# EDA_AD__2021-08-16.net
KiCad netlist of a schematic drawn in Altium Designer
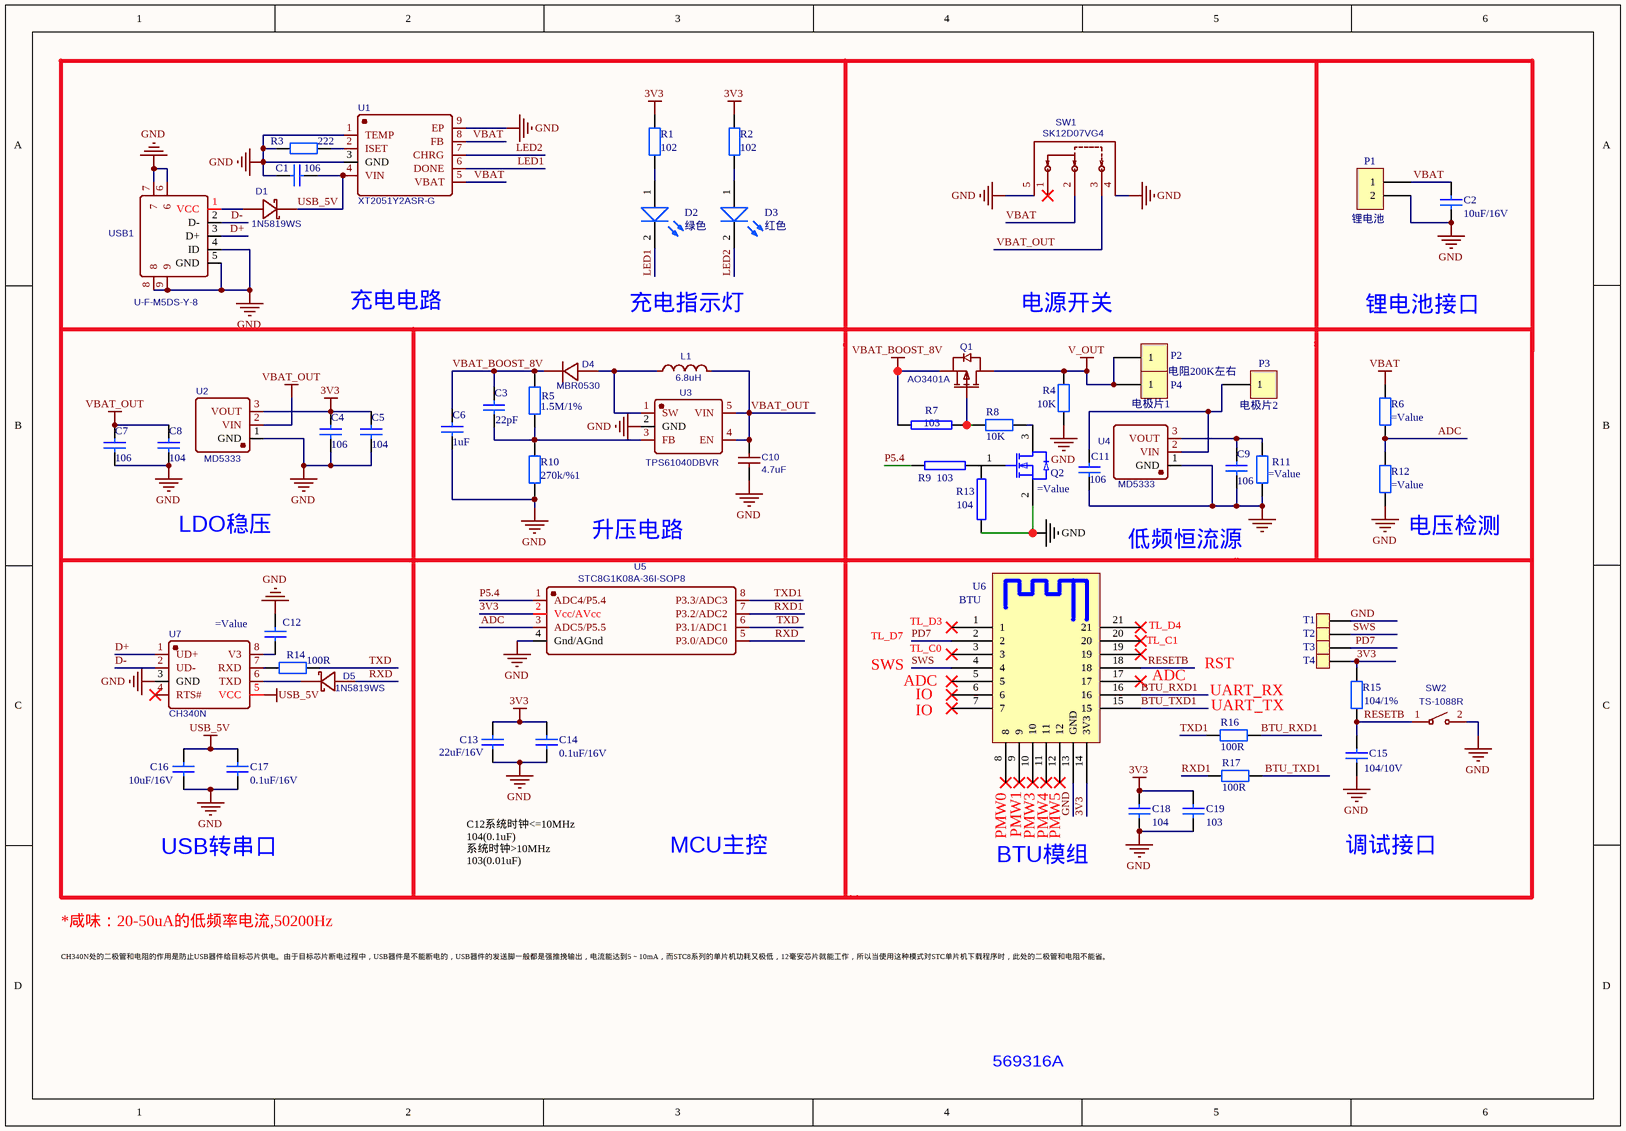
[diagram p0: 百味勺子（立创EDA、AD）_2021-08-16.schdoc]

(export (version "E")
  (design (tool "Eeschema 10.0.6"))
  (components
    (comp (ref "C1")
      (value "1uF/16V")
      (fields (field (name "PART NUMBER") "1.02.03.00181") (field (name "修改人") "system"))
      (libsource (lib "altium-import") (part "root_2_1uF/16V_"))
    )
    (comp (ref "C2")
      (value "10uF/16V")
      (fields (field (name "PART NUMBER") "1.02.05.00869"))
      (libsource (lib "altium-import") (part "root_3_10uF/16V_"))
    )
    (comp (ref "C3")
      (value "22pF")
      (fields (field (name "PART NUMBER") "1.02.05.00869"))
      (libsource (lib "altium-import") (part "root_3_22pF_"))
    )
    (comp (ref "C4")
      (value "106")
      (fields (field (name "PART NUMBER") "1.02.05.00869"))
      (libsource (lib "altium-import") (part "root_3_106_"))
    )
    (comp (ref "C5")
      (value "104")
      (fields (field (name "PART NUMBER") "1.02.05.00869"))
      (libsource (lib "altium-import") (part "root_3_104_"))
    )
    (comp (ref "C6")
      (value "1uF")
      (fields (field (name "PART NUMBER") "1.02.05.00869"))
      (libsource (lib "altium-import") (part "root_3_1uF_"))
    )
    (comp (ref "C7")
      (value "106")
      (fields (field (name "PART NUMBER") "1.02.05.00869"))
      (libsource (lib "altium-import") (part "root_3_106_"))
    )
    (comp (ref "C8")
      (value "104")
      (fields (field (name "PART NUMBER") "1.02.05.00869"))
      (libsource (lib "altium-import") (part "root_3_104_"))
    )
    (comp (ref "C9")
      (value "106")
      (fields (field (name "PART NUMBER") "1.02.05.00869"))
      (libsource (lib "altium-import") (part "root_3_106_"))
    )
    (comp (ref "C10")
      (value "4.7uF")
      (fields
        (field (name "BOM_MANUFACTURER PART") "JMK212BJ475KG-T")
        (field (name "BOM_SUPPLIER PART") "C92788")
      )
      (libsource (lib "altium-import") (part "root_1_4.7uF_"))
    )
    (comp (ref "C11")
      (value "106")
      (fields (field (name "PART NUMBER") "1.02.05.00869"))
      (libsource (lib "altium-import") (part "root_3_106_"))
    )
    (comp (ref "C12")
      (value "0.1uF/50V")
      (fields (field (name "PART NUMBER") "1.02.05.00834") (field (name "修改人") "system"))
      (libsource (lib "altium-import") (part "root_1_0.1uF/50V_"))
    )
    (comp (ref "C13")
      (value "1uF/16V")
      (fields (field (name "PART NUMBER") "1.02.03.00181") (field (name "修改人") "system"))
      (libsource (lib "altium-import") (part "root_1_1uF/16V_"))
    )
    (comp (ref "C14")
      (value "0.1uF/50V")
      (fields (field (name "PART NUMBER") "1.02.05.00834") (field (name "修改人") "system"))
      (libsource (lib "altium-import") (part "root_1_0.1uF/50V_"))
    )
    (comp (ref "C15")
      (value "104/10V")
      (fields (field (name "PART NUMBER") "1.02.05.00869"))
      (libsource (lib "altium-import") (part "root_3_104/10V_"))
    )
    (comp (ref "C16")
      (value "1uF/16V")
      (fields (field (name "PART NUMBER") "1.02.03.00181") (field (name "修改人") "system"))
      (libsource (lib "altium-import") (part "root_1_1uF/16V_"))
    )
    (comp (ref "C17")
      (value "0.1uF/50V")
      (fields (field (name "PART NUMBER") "1.02.05.00834") (field (name "修改人") "system"))
      (libsource (lib "altium-import") (part "root_1_0.1uF/50V_"))
    )
    (comp (ref "C18")
      (value "104")
      (fields (field (name "PART NUMBER") "1.02.05.00869"))
      (libsource (lib "altium-import") (part "root_3_104_"))
    )
    (comp (ref "C19")
      (value "103")
      (fields (field (name "PART NUMBER") "1.02.05.00869"))
      (libsource (lib "altium-import") (part "root_3_103_"))
    )
    (comp (ref "D1")
      (value "1N5819WS")
      (fields (field (name "BOM_SUPPLIER PART") "C1884554") (field (name "CONTRIBUTOR") "LCSC"))
      (libsource (lib "altium-import") (part "root_2_1N5819WS_"))
    )
    (comp (ref "D2")
      (value "绿色")
      (fields (field (name "PART NUMBER") "1.06.02.00452"))
      (libsource (lib "altium-import") (part "root_3_绿色_"))
    )
    (comp (ref "D3")
      (value "红色")
      (fields (field (name "PART NUMBER") "1.06.02.00452"))
      (libsource (lib "altium-import") (part "root_3_红色_"))
    )
    (comp (ref "D4")
      (value "MBR0530")
      (fields (field (name "BOM_SUPPLIER PART") "C475718") (field (name "CONTRIBUTOR") "LCSC"))
      (libsource (lib "altium-import") (part "root_0_MBR0530_"))
    )
    (comp (ref "D5")
      (value "1N5819WS")
      (fields (field (name "BOM_SUPPLIER PART") "C1884554") (field (name "CONTRIBUTOR") "LCSC"))
      (libsource (lib "altium-import") (part "root_0_1N5819WS_"))
    )
    (comp (ref "L1")
      (value "6.8uH")
      (fields
        (field (name "BOM_SUPPLIER PART") "C323532")
        (field (name "BOM_MANUFACTURER PART") "CDRH3D23NP-6R8PC")
        (field (name "CONTRIBUTOR") "LCSC")
      )
      (libsource (lib "altium-import") (part "root_0_6.8uH_"))
    )
    (comp (ref "P1") (value "锂电池") (libsource (lib "altium-import") (part "root_0_锂电池_")))
    (comp (ref "P2") (value "CON1") (libsource (lib "altium-import") (part "root_0_CON1_")))
    (comp (ref "P3") (value "CON1") (libsource (lib "altium-import") (part "root_0_CON1_")))
    (comp (ref "P4") (value "CON1") (libsource (lib "altium-import") (part "root_0_CON1_")))
    (comp (ref "Q1")
      (value "AO3401A")
      (fields (field (name "BOM_SUPPLIER PART") "C700954") (field (name "CONTRIBUTOR") "LCSC"))
      (libsource (lib "altium-import") (part "root_1_AO3401A_"))
    )
    (comp (ref "Q2")
      (value "CJ2312")
      (fields
        (field (name "PART NUMBER") "1.06.11.00008")
        (field (name "ORCAD LIBRARY PATH") "‪Z:\\tuya_lib\\sch-lib\\DISCRETE.OLB")
        (field (name "修改人") "system")
      )
      (libsource (lib "altium-import") (part "root_0_CJ2312_"))
    )
    (comp (ref "R1")
      (value "102")
      (fields (field (name "PART NUMBER") "1.01.01.00808"))
      (libsource (lib "altium-import") (part "root_1_102_"))
    )
    (comp (ref "R2")
      (value "102")
      (fields (field (name "PART NUMBER") "1.01.01.00808"))
      (libsource (lib "altium-import") (part "root_1_102_"))
    )
    (comp (ref "R3")
      (value "222")
      (fields (field (name "PART NUMBER") "1.01.01.00808"))
      (libsource (lib "altium-import") (part "root_2_222_"))
    )
    (comp (ref "R4") (value "100K/1%") (libsource (lib "altium-import") (part "root_3_100K/1%_")))
    (comp (ref "R5") (value "100K/1%") (libsource (lib "altium-import") (part "root_1_100K/1%_")))
    (comp (ref "R6") (value "100K/1%") (libsource (lib "altium-import") (part "root_1_100K/1%_")))
    (comp (ref "R7") (value "103") (libsource (lib "altium-import") (part "root_0_103_")))
    (comp (ref "R8") (value "100K/1%") (libsource (lib "altium-import") (part "root_0_100K/1%_")))
    (comp (ref "R9") (value "103") (libsource (lib "altium-import") (part "root_0_103_")))
    (comp (ref "R10") (value "100K/1%") (libsource (lib "altium-import") (part "root_1_100K/1%_")))
    (comp (ref "R11") (value "100K/1%") (libsource (lib "altium-import") (part "root_1_100K/1%_")))
    (comp (ref "R12") (value "100K/1%") (libsource (lib "altium-import") (part "root_1_100K/1%_")))
    (comp (ref "R13") (value "104") (libsource (lib "altium-import") (part "root_1_104_")))
    (comp (ref "R14")
      (value "200R")
      (fields (field (name "PART NUMBER") "1.01.01.00808") (field (name "修改人") "system"))
      (libsource (lib "altium-import") (part "root_0_200R_"))
    )
    (comp (ref "R15")
      (value "104/1%")
      (fields (field (name "PART NUMBER") "1.01.01.00808"))
      (libsource (lib "altium-import") (part "root_1_104/1%_"))
    )
    (comp (ref "R16")
      (value "100R")
      (fields (field (name "PART NUMBER") "1.01.01.00808"))
      (libsource (lib "altium-import") (part "root_2_100R_"))
    )
    (comp (ref "R17")
      (value "100R")
      (fields (field (name "PART NUMBER") "1.01.01.00808"))
      (libsource (lib "altium-import") (part "root_2_100R_"))
    )
    (comp (ref "SW1")
      (value "SK12D07VG4")
      (fields (field (name "BOM_SUPPLIER PART") "C393937") (field (name "CONTRIBUTOR") "LCSC"))
      (libsource (lib "altium-import") (part "root_0_SK12D07VG4_"))
    )
    (comp (ref "SW2")
      (value "TS-1088R")
      (fields
        (field (name "BOM_SUPPLIER PART") "C455280")
        (field (name "BOM_MANUFACTURER PART") "TS-1088R-02026")
        (field (name "CONTRIBUTOR") "LCSC")
      )
      (libsource (lib "altium-import") (part "root_0_TS-1088R_"))
    )
    (comp (ref "T1") (value "TP") (libsource (lib "altium-import") (part "root_0_TP_")))
    (comp (ref "T2") (value "TP") (libsource (lib "altium-import") (part "root_0_TP_")))
    (comp (ref "T3") (value "TP") (libsource (lib "altium-import") (part "root_0_TP_")))
    (comp (ref "T4") (value "TP") (libsource (lib "altium-import") (part "root_0_TP_")))
    (comp (ref "U1")
      (value "XT2051Y2ASR-G")
      (fields (field (name "BOM_SUPPLIER PART") "C236398") (field (name "CONTRIBUTOR") "LCSC"))
      (libsource (lib "altium-import") (part "root_0_XT2051Y2ASR-G_"))
    )
    (comp (ref "U2")
      (value "MD5333")
      (fields (field (name "BOM_SUPPLIER PART") "C2827936") (field (name "CONTRIBUTOR") "LCSC"))
      (libsource (lib "altium-import") (part "root_2_MD5333_"))
    )
    (comp (ref "U3")
      (value "TPS61040DBVR")
      (fields (field (name "BOM_SUPPLIER PART") "C7722"))
      (libsource (lib "altium-import") (part "root_0_TPS61040DBVR_"))
    )
    (comp (ref "U4")
      (value "MD5333")
      (fields (field (name "BOM_SUPPLIER PART") "C2827936") (field (name "CONTRIBUTOR") "LCSC"))
      (libsource (lib "altium-import") (part "root_2_MD5333_"))
    )
    (comp (ref "U5")
      (value "STC8G1K08A-36I-SOP8")
      (fields (field (name "BOM_SUPPLIER PART") "C915663") (field (name "CONTRIBUTOR") "LCSC"))
      (libsource (lib "altium-import") (part "root_0_STC8G1K08A-36I-SOP8_"))
    )
    (comp (ref "U6")
      (value "CBU")
      (fields (field (name "PART NUMBER") "0110"))
      (libsource (lib "altium-import") (part "root_0_CBU_"))
    )
    (comp (ref "U7")
      (value "CH340N")
      (fields (field (name "BOM_SUPPLIER PART") "C506813") (field (name "CONTRIBUTOR") "LCSC"))
      (libsource (lib "altium-import") (part "root_0_CH340N_"))
    )
    (comp (ref "USB1")
      (value "U-F-M5DS-Y-8")
      (fields (field (name "BOM_SUPPLIER PART") "C961761") (field (name "CONTRIBUTOR") "LCSC"))
      (libsource (lib "altium-import") (part "root_0_U-F-M5DS-Y-8_"))
    )
  )
  (nets
    (net (code "1") (name "/ADC") (class "Default")
      (node (ref "R12") (pin "2") (pinfunction "2_2") (pintype "passive"))
      (node (ref "R6") (pin "1") (pinfunction "1_1") (pintype "passive"))
      (node (ref "U5") (pin "3") (pinfunction "ADC5/P5.5_3") (pintype "passive"))
    )
    (net (code "2") (name "/BTU_RXD1") (class "Default")
      (node (ref "R16") (pin "1") (pinfunction "1_1") (pintype "passive"))
      (node (ref "U6") (pin "16") (pinfunction "16_16") (pintype "passive"))
    )
    (net (code "3") (name "/BTU_TXD1") (class "Default")
      (node (ref "R17") (pin "1") (pinfunction "1_1") (pintype "passive"))
      (node (ref "U6") (pin "15") (pinfunction "15_15") (pintype "passive"))
    )
    (net (code "4") (name "/D+") (class "Default")
      (node (ref "U7") (pin "1") (pinfunction "UD+_1") (pintype "passive"))
      (node (ref "USB1") (pin "3") (pinfunction "D+_3") (pintype "passive"))
    )
    (net (code "5") (name "/D-") (class "Default")
      (node (ref "U7") (pin "2") (pinfunction "UD-_2") (pintype "passive"))
      (node (ref "USB1") (pin "2") (pinfunction "D-_2") (pintype "passive"))
    )
    (net (code "6") (name "/LED1") (class "Default")
      (node (ref "D2") (pin "2") (pinfunction "2_2") (pintype "passive"))
      (node (ref "U1") (pin "6") (pinfunction "DONE_6") (pintype "passive"))
    )
    (net (code "7") (name "/LED2") (class "Default")
      (node (ref "D3") (pin "2") (pinfunction "2_2") (pintype "passive"))
      (node (ref "U1") (pin "7") (pinfunction "CHRG_7") (pintype "passive"))
    )
    (net (code "8") (name "/P5.4") (class "Default")
      (node (ref "R9") (pin "1") (pintype "passive"))
      (node (ref "U5") (pin "1") (pinfunction "ADC4/P5.4_1") (pintype "passive"))
    )
    (net (code "9") (name "/PD7") (class "Default")
      (node (ref "T3") (pin "1") (pinfunction "1_1") (pintype "passive"))
      (node (ref "U6") (pin "2") (pinfunction "2_2") (pintype "passive"))
    )
    (net (code "10") (name "/RESETB") (class "Default")
      (node (ref "C15") (pin "1") (pinfunction "1_1") (pintype "passive"))
      (node (ref "R15") (pin "1") (pinfunction "1_1") (pintype "passive"))
      (node (ref "SW2") (pin "1") (pinfunction "1_1") (pintype "passive"))
      (node (ref "U6") (pin "18") (pinfunction "18_18") (pintype "passive"))
    )
    (net (code "11") (name "/RXD") (class "Default")
      (node (ref "D5") (pin "2") (pinfunction "A_2") (pintype "passive"))
      (node (ref "U5") (pin "5") (pinfunction "P3.0/ADC0_5") (pintype "passive"))
    )
    (net (code "12") (name "/RXD1") (class "Default")
      (node (ref "R17") (pin "2") (pinfunction "2_2") (pintype "passive"))
      (node (ref "U5") (pin "7") (pinfunction "P3.2/ADC2_7") (pintype "passive"))
    )
    (net (code "13") (name "/SWS") (class "Default")
      (node (ref "T2") (pin "1") (pinfunction "1_1") (pintype "passive"))
      (node (ref "U6") (pin "4") (pinfunction "4_4") (pintype "passive"))
    )
    (net (code "14") (name "/TXD") (class "Default")
      (node (ref "R14") (pin "2") (pinfunction "2_2") (pintype "passive"))
      (node (ref "U5") (pin "6") (pinfunction "P3.1/ADC1_6") (pintype "passive"))
    )
    (net (code "15") (name "/TXD1") (class "Default")
      (node (ref "R16") (pin "2") (pinfunction "2_2") (pintype "passive"))
      (node (ref "U5") (pin "8") (pinfunction "P3.3/ADC3_8") (pintype "passive"))
    )
    (net (code "16") (name "3V3") (class "Default")
      (node (ref "C13") (pin "2") (pinfunction "2_2") (pintype "passive"))
      (node (ref "C14") (pin "2") (pinfunction "2_2") (pintype "passive"))
      (node (ref "C18") (pin "1") (pinfunction "1_1") (pintype "passive"))
      (node (ref "C19") (pin "1") (pinfunction "1_1") (pintype "passive"))
      (node (ref "C4") (pin "1") (pinfunction "1_1") (pintype "passive"))
      (node (ref "C5") (pin "1") (pinfunction "1_1") (pintype "passive"))
      (node (ref "R1") (pin "2") (pinfunction "2_2") (pintype "passive"))
      (node (ref "R15") (pin "2") (pinfunction "2_2") (pintype "passive"))
      (node (ref "R2") (pin "2") (pinfunction "2_2") (pintype "passive"))
      (node (ref "T4") (pin "1") (pinfunction "1_1") (pintype "passive"))
      (node (ref "U2") (pin "3") (pinfunction "VOUT_3") (pintype "passive"))
      (node (ref "U5") (pin "2") (pinfunction "Vcc/AVcc_2") (pintype "passive"))
      (node (ref "U6") (pin "14") (pinfunction "3V3_14") (pintype "passive"))
    )
    (net (code "17") (name "GND") (class "Default")
      (node (ref "C1") (pin "2") (pinfunction "2_2") (pintype "passive"))
      (node (ref "C10") (pin "1") (pinfunction "1_1") (pintype "passive"))
      (node (ref "C11") (pin "2") (pinfunction "2_2") (pintype "passive"))
      (node (ref "C12") (pin "2") (pinfunction "2_2") (pintype "passive"))
      (node (ref "C13") (pin "1") (pinfunction "1_1") (pintype "passive"))
      (node (ref "C14") (pin "1") (pinfunction "1_1") (pintype "passive"))
      (node (ref "C15") (pin "2") (pinfunction "2_2") (pintype "passive"))
      (node (ref "C16") (pin "1") (pinfunction "1_1") (pintype "passive"))
      (node (ref "C17") (pin "1") (pinfunction "1_1") (pintype "passive"))
      (node (ref "C18") (pin "2") (pinfunction "2_2") (pintype "passive"))
      (node (ref "C19") (pin "2") (pinfunction "2_2") (pintype "passive"))
      (node (ref "C2") (pin "2") (pinfunction "2_2") (pintype "passive"))
      (node (ref "C4") (pin "2") (pinfunction "2_2") (pintype "passive"))
      (node (ref "C5") (pin "2") (pinfunction "2_2") (pintype "passive"))
      (node (ref "C6") (pin "2") (pinfunction "2_2") (pintype "passive"))
      (node (ref "C7") (pin "2") (pinfunction "2_2") (pintype "passive"))
      (node (ref "C8") (pin "2") (pinfunction "2_2") (pintype "passive"))
      (node (ref "C9") (pin "2") (pinfunction "2_2") (pintype "passive"))
      (node (ref "P1") (pin "2") (pinfunction "2_2") (pintype "passive"))
      (node (ref "Q2") (pin "2") (pinfunction "S_2") (pintype "passive"))
      (node (ref "R10") (pin "1") (pinfunction "1_1") (pintype "passive"))
      (node (ref "R11") (pin "1") (pinfunction "1_1") (pintype "passive"))
      (node (ref "R12") (pin "1") (pinfunction "1_1") (pintype "passive"))
      (node (ref "R13") (pin "1") (pintype "passive"))
      (node (ref "R3") (pin "2") (pinfunction "2_2") (pintype "passive"))
      (node (ref "R4") (pin "2") (pinfunction "2_2") (pintype "passive"))
      (node (ref "SW1") (pin "4") (pinfunction "4_4") (pintype "passive"))
      (node (ref "SW1") (pin "5") (pinfunction "5_5") (pintype "passive"))
      (node (ref "SW2") (pin "2") (pinfunction "2_2") (pintype "passive"))
      (node (ref "T1") (pin "1") (pinfunction "1_1") (pintype "passive"))
      (node (ref "U1") (pin "1") (pinfunction "TEMP_1") (pintype "passive"))
      (node (ref "U1") (pin "3") (pinfunction "GND_3") (pintype "passive"))
      (node (ref "U1") (pin "9") (pinfunction "EP_9") (pintype "passive"))
      (node (ref "U2") (pin "1") (pinfunction "GND_1") (pintype "passive"))
      (node (ref "U3") (pin "2") (pinfunction "GND_2") (pintype "passive"))
      (node (ref "U4") (pin "1") (pinfunction "GND_1") (pintype "passive"))
      (node (ref "U5") (pin "4") (pinfunction "Gnd/AGnd_4") (pintype "passive"))
      (node (ref "U6") (pin "13") (pinfunction "GND_13") (pintype "passive"))
      (node (ref "U7") (pin "3") (pinfunction "GND_3") (pintype "passive"))
      (node (ref "USB1") (pin "4") (pinfunction "ID_4") (pintype "passive"))
      (node (ref "USB1") (pin "5") (pinfunction "GND_5") (pintype "passive"))
      (node (ref "USB1") (pin "6") (pinfunction "6_6") (pintype "passive"))
      (node (ref "USB1") (pin "7") (pinfunction "7_7") (pintype "passive"))
      (node (ref "USB1") (pin "8") (pinfunction "8_8") (pintype "passive"))
      (node (ref "USB1") (pin "9") (pinfunction "9_9") (pintype "passive"))
    )
    (net (code "18") (name "Net-(D1-A)") (class "Default")
      (node (ref "D1") (pin "2") (pinfunction "A_2") (pintype "passive"))
      (node (ref "USB1") (pin "1") (pinfunction "VCC_1") (pintype "passive"))
    )
    (net (code "19") (name "Net-(D2-Pad1)") (class "Default")
      (node (ref "D2") (pin "1") (pinfunction "1_1") (pintype "passive"))
      (node (ref "R1") (pin "1") (pinfunction "1_1") (pintype "passive"))
    )
    (net (code "20") (name "Net-(D3-Pad1)") (class "Default")
      (node (ref "D3") (pin "1") (pinfunction "1_1") (pintype "passive"))
      (node (ref "R2") (pin "1") (pinfunction "1_1") (pintype "passive"))
    )
    (net (code "21") (name "Net-(D4-A)") (class "Default")
      (node (ref "D4") (pin "2") (pinfunction "A_2") (pintype "passive"))
      (node (ref "L1") (pin "1") (pinfunction "1_1") (pintype "passive"))
      (node (ref "U3") (pin "1") (pinfunction "SW_1") (pintype "passive"))
    )
    (net (code "22") (name "Net-(D5-C)") (class "Default")
      (node (ref "D5") (pin "1") (pinfunction "C_1") (pintype "passive"))
      (node (ref "U7") (pin "6") (pinfunction "TXD_6") (pintype "passive"))
    )
    (net (code "23") (name "Net-(Q1-G)") (class "Default")
      (node (ref "Q1") (pin "1") (pinfunction "G_1") (pintype "passive"))
      (node (ref "R7") (pin "2") (pintype "passive"))
      (node (ref "R8") (pin "1") (pinfunction "1_1") (pintype "passive"))
    )
    (net (code "24") (name "Net-(Q2-D)") (class "Default")
      (node (ref "Q2") (pin "3") (pinfunction "D_3") (pintype "passive"))
      (node (ref "R8") (pin "2") (pinfunction "2_2") (pintype "passive"))
    )
    (net (code "25") (name "Net-(Q2-G)") (class "Default")
      (node (ref "Q2") (pin "1") (pinfunction "G_1") (pintype "passive"))
      (node (ref "R9") (pin "2") (pintype "passive"))
    )
    (net (code "26") (name "Net-(U1-ISET)") (class "Default")
      (node (ref "R3") (pin "1") (pinfunction "1_1") (pintype "passive"))
      (node (ref "U1") (pin "2") (pinfunction "ISET_2") (pintype "passive"))
    )
    (net (code "27") (name "Net-(U3-FB)") (class "Default")
      (node (ref "C3") (pin "2") (pinfunction "2_2") (pintype "passive"))
      (node (ref "R10") (pin "2") (pinfunction "2_2") (pintype "passive"))
      (node (ref "R5") (pin "1") (pinfunction "1_1") (pintype "passive"))
      (node (ref "U3") (pin "3") (pinfunction "FB_3") (pintype "passive"))
    )
    (net (code "28") (name "Net-(U4-VIN)") (class "Default")
      (node (ref "C11") (pin "1") (pinfunction "1_1") (pintype "passive"))
      (node (ref "P3") (pin "1") (pinfunction "1_1") (pintype "passive"))
      (node (ref "U4") (pin "2") (pinfunction "VIN_2") (pintype "passive"))
    )
    (net (code "29") (name "Net-(U4-VOUT)") (class "Default")
      (node (ref "C9") (pin "1") (pinfunction "1_1") (pintype "passive"))
      (node (ref "R11") (pin "2") (pinfunction "2_2") (pintype "passive"))
      (node (ref "U4") (pin "3") (pinfunction "VOUT_3") (pintype "passive"))
    )
    (net (code "30") (name "Net-(U7-RXD)") (class "Default")
      (node (ref "R14") (pin "1") (pinfunction "1_1") (pintype "passive"))
      (node (ref "U7") (pin "7") (pinfunction "RXD_7") (pintype "passive"))
    )
    (net (code "31") (name "Net-(U7-V3)") (class "Default")
      (node (ref "C12") (pin "1") (pinfunction "1_1") (pintype "passive"))
      (node (ref "U7") (pin "8") (pinfunction "V3_8") (pintype "passive"))
    )
    (net (code "32") (name "USB_5V") (class "Default")
      (node (ref "C1") (pin "1") (pinfunction "1_1") (pintype "passive"))
      (node (ref "C16") (pin "2") (pinfunction "2_2") (pintype "passive"))
      (node (ref "C17") (pin "2") (pinfunction "2_2") (pintype "passive"))
      (node (ref "D1") (pin "1") (pinfunction "C_1") (pintype "passive"))
      (node (ref "U1") (pin "4") (pinfunction "VIN_4") (pintype "passive"))
      (node (ref "U7") (pin "5") (pinfunction "VCC_5") (pintype "passive"))
    )
    (net (code "33") (name "VBAT") (class "Default")
      (node (ref "C2") (pin "1") (pinfunction "1_1") (pintype "passive"))
      (node (ref "P1") (pin "1") (pinfunction "1_1") (pintype "passive"))
      (node (ref "R6") (pin "2") (pinfunction "2_2") (pintype "passive"))
      (node (ref "SW1") (pin "2") (pinfunction "2_2") (pintype "passive"))
      (node (ref "U1") (pin "5") (pinfunction "VBAT_5") (pintype "passive"))
      (node (ref "U1") (pin "8") (pinfunction "FB_8") (pintype "passive"))
    )
    (net (code "34") (name "VBAT_BOOST_8V") (class "Default")
      (node (ref "C3") (pin "1") (pinfunction "1_1") (pintype "passive"))
      (node (ref "C6") (pin "1") (pinfunction "1_1") (pintype "passive"))
      (node (ref "D4") (pin "1") (pinfunction "K_1") (pintype "passive"))
      (node (ref "Q1") (pin "2") (pinfunction "S_2") (pintype "passive"))
      (node (ref "R5") (pin "2") (pinfunction "2_2") (pintype "passive"))
      (node (ref "R7") (pin "1") (pintype "passive"))
    )
    (net (code "35") (name "VBAT_OUT") (class "Default")
      (node (ref "C10") (pin "2") (pinfunction "2_2") (pintype "passive"))
      (node (ref "C7") (pin "1") (pinfunction "1_1") (pintype "passive"))
      (node (ref "C8") (pin "1") (pinfunction "1_1") (pintype "passive"))
      (node (ref "L1") (pin "2") (pinfunction "2_2") (pintype "passive"))
      (node (ref "SW1") (pin "3") (pinfunction "3_3") (pintype "passive"))
      (node (ref "U2") (pin "2") (pinfunction "VIN_2") (pintype "passive"))
      (node (ref "U3") (pin "4") (pinfunction "EN_4") (pintype "passive"))
      (node (ref "U3") (pin "5") (pinfunction "VIN_5") (pintype "passive"))
    )
    (net (code "36") (name "V_OUT") (class "Default")
      (node (ref "P2") (pin "1") (pinfunction "1_1") (pintype "passive"))
      (node (ref "P4") (pin "1") (pinfunction "1_1") (pintype "passive"))
      (node (ref "Q1") (pin "3") (pinfunction "D_3") (pintype "passive"))
      (node (ref "R4") (pin "1") (pinfunction "1_1") (pintype "passive"))
    )
    (net (code "37") (name "unconnected-(R13-Pad2)") (class "Default")
      (node (ref "R13") (pin "2") (pintype "passive"))
    )
    (net (code "38") (name "unconnected-(SW1-Pad1)") (class "Default")
      (node (ref "SW1") (pin "1") (pinfunction "1_1") (pintype "passive+no_connect"))
    )
    (net (code "39") (name "unconnected-(U6-Pad1)") (class "Default")
      (node (ref "U6") (pin "1") (pinfunction "1_1") (pintype "passive+no_connect"))
    )
    (net (code "40") (name "unconnected-(U6-Pad3)") (class "Default")
      (node (ref "U6") (pin "3") (pinfunction "3_3") (pintype "passive+no_connect"))
    )
    (net (code "41") (name "unconnected-(U6-Pad5)") (class "Default")
      (node (ref "U6") (pin "5") (pinfunction "5_5") (pintype "passive+no_connect"))
    )
    (net (code "42") (name "unconnected-(U6-Pad6)") (class "Default")
      (node (ref "U6") (pin "6") (pinfunction "6_6") (pintype "passive+no_connect"))
    )
    (net (code "43") (name "unconnected-(U6-Pad7)") (class "Default")
      (node (ref "U6") (pin "7") (pinfunction "7_7") (pintype "passive+no_connect"))
    )
    (net (code "44") (name "unconnected-(U6-Pad8)") (class "Default")
      (node (ref "U6") (pin "8") (pinfunction "8_8") (pintype "passive+no_connect"))
    )
    (net (code "45") (name "unconnected-(U6-Pad9)") (class "Default")
      (node (ref "U6") (pin "9") (pinfunction "9_9") (pintype "passive+no_connect"))
    )
    (net (code "46") (name "unconnected-(U6-Pad10)") (class "Default")
      (node (ref "U6") (pin "10") (pinfunction "10_10") (pintype "passive+no_connect"))
    )
    (net (code "47") (name "unconnected-(U6-Pad11)") (class "Default")
      (node (ref "U6") (pin "11") (pinfunction "11_11") (pintype "passive+no_connect"))
    )
    (net (code "48") (name "unconnected-(U6-Pad12)") (class "Default")
      (node (ref "U6") (pin "12") (pinfunction "12_12") (pintype "passive+no_connect"))
    )
    (net (code "49") (name "unconnected-(U6-Pad17)") (class "Default")
      (node (ref "U6") (pin "17") (pinfunction "17_17") (pintype "passive+no_connect"))
    )
    (net (code "50") (name "unconnected-(U6-Pad19)") (class "Default")
      (node (ref "U6") (pin "19") (pinfunction "19_19") (pintype "passive+no_connect"))
    )
    (net (code "51") (name "unconnected-(U6-Pad20)") (class "Default")
      (node (ref "U6") (pin "20") (pinfunction "20_20") (pintype "passive+no_connect"))
    )
    (net (code "52") (name "unconnected-(U6-Pad21)") (class "Default")
      (node (ref "U6") (pin "21") (pinfunction "21_21") (pintype "passive+no_connect"))
    )
    (net (code "53") (name "unconnected-(U7-RTS#-Pad4)") (class "Default")
      (node (ref "U7") (pin "4") (pinfunction "RTS#_4") (pintype "passive+no_connect"))
    )
  )
)
